# AntennaSide.net
KiCad netlist of a schematic drawn in Altium Designer
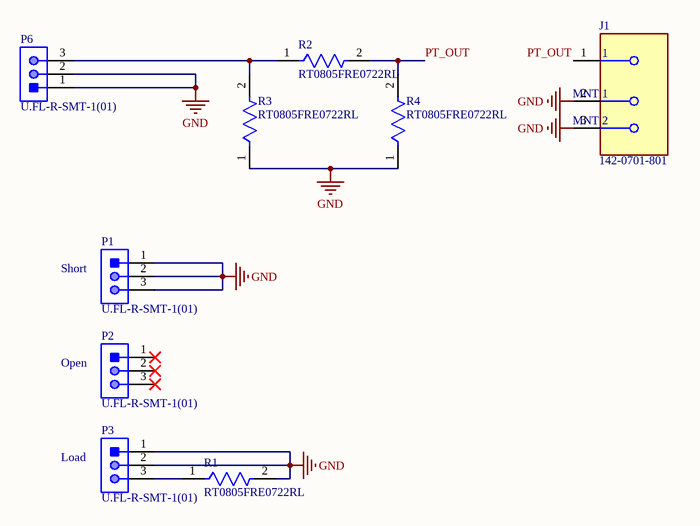
[diagram p0: AntennaSide.SchDoc]

(export (version "E")
  (design (tool "Eeschema 10.0.6"))
  (components
    (comp (ref "J1")
      (value "142-0701-801")
      (footprint "FP-142-0701-801-MFG")
      (description "CONN SMA JACK STR 50OHM EDGE MNT")
      (libsource (lib "Altium Content Vault") (part "89929399afe843c8b6880c6cbd0f99a"))
    )
    (comp (ref "P1")
      (value "U.FL-R-SMT-1(01)")
      (footprint "HRS-U.FL-R-SMT-3_V")
      (description "Ultra Small Coaxial Connector, 6 GHz, -40 to 90 degC, 3-Pin SMD, RoHS, Bulk")
      (fields (field (name "MANUFACTURER") "Hirose Electric"))
      (libsource (lib "Altium Content Vault") (part "CN-1P-M-R3"))
    )
    (comp (ref "P2")
      (value "U.FL-R-SMT-1(01)")
      (footprint "HRS-U.FL-R-SMT-3_V")
      (description "Ultra Small Coaxial Connector, 6 GHz, -40 to 90 degC, 3-Pin SMD, RoHS, Bulk")
      (fields (field (name "MANUFACTURER") "Hirose Electric"))
      (libsource (lib "Altium Content Vault") (part "CN-1P-M-R3"))
    )
    (comp (ref "P3")
      (value "U.FL-R-SMT-1(01)")
      (footprint "HRS-U.FL-R-SMT-3_V")
      (description "Ultra Small Coaxial Connector, 6 GHz, -40 to 90 degC, 3-Pin SMD, RoHS, Bulk")
      (fields (field (name "MANUFACTURER") "Hirose Electric"))
      (libsource (lib "Altium Content Vault") (part "CN-1P-M-R3"))
    )
    (comp (ref "P6")
      (value "U.FL-R-SMT-1(01)")
      (footprint "HRS-U.FL-R-SMT-3_V")
      (description "Ultra Small Coaxial Connector, 6 GHz, -40 to 90 degC, 3-Pin SMD, RoHS, Bulk")
      (fields (field (name "MANUFACTURER") "Hirose Electric"))
      (libsource (lib "") (part "CN-1P-M-R3_1"))
    )
    (comp (ref "R1")
      (value "RT0805FRE0722RL")
      (footprint "FP-RT0805-MFG")
      (description "RES SMD 22 OHM 1% 1/8W 0805")
      (fields
        (field (name "OCTOPART") "https://octopart.com/rt0805fre0722rl-yageo-39984181")
        (field (name "MANUFACTURER") "Yageo")
      )
      (libsource (lib "Altium Content Vault") (part "1029c3af85768c4190bb7ad29bc67b5"))
    )
    (comp (ref "R2")
      (value "RT0805FRE0722RL")
      (footprint "FP-RT0805-MFG")
      (description "RES SMD 22 OHM 1% 1/8W 0805")
      (fields
        (field (name "OCTOPART") "https://octopart.com/rt0805fre0722rl-yageo-39984181")
        (field (name "MANUFACTURER") "Yageo")
      )
      (libsource (lib "Altium Content Vault") (part "1029c3af85768c4190bb7ad29bc67b5"))
    )
    (comp (ref "R3")
      (value "RT0805FRE0722RL")
      (footprint "FP-RT0805-MFG")
      (description "RES SMD 22 OHM 1% 1/8W 0805")
      (fields
        (field (name "OCTOPART") "https://octopart.com/rt0805fre0722rl-yageo-39984181")
        (field (name "MANUFACTURER") "Yageo")
      )
      (libsource (lib "Altium Content Vault") (part "1029c3af85768c4190bb7ad29bc67b5"))
    )
    (comp (ref "R4")
      (value "RT0805FRE0722RL")
      (footprint "FP-RT0805-MFG")
      (description "RES SMD 22 OHM 1% 1/8W 0805")
      (fields
        (field (name "OCTOPART") "https://octopart.com/rt0805fre0722rl-yageo-39984181")
        (field (name "MANUFACTURER") "Yageo")
      )
      (libsource (lib "Altium Content Vault") (part "1029c3af85768c4190bb7ad29bc67b5"))
    )
  )
  (nets
    (net (code "1") (name "/PT_OUT") (class "Default")
      (node (ref "J1") (pin "1") (pinfunction "1_1") (pintype "passive"))
      (node (ref "R2") (pin "2") (pinfunction "2_2") (pintype "passive"))
      (node (ref "R4") (pin "2") (pinfunction "2_2") (pintype "passive"))
    )
    (net (code "2") (name "GND") (class "Default")
      (node (ref "J1") (pin "2") (pinfunction "MNT_1_2") (pintype "passive"))
      (node (ref "J1") (pin "3") (pinfunction "MNT_2_3") (pintype "passive"))
      (node (ref "P1") (pin "1") (pinfunction "1_1") (pintype "passive"))
      (node (ref "P1") (pin "2") (pinfunction "2_2") (pintype "passive"))
      (node (ref "P1") (pin "3") (pinfunction "3_3") (pintype "passive"))
      (node (ref "P3") (pin "1") (pinfunction "1_1") (pintype "passive"))
      (node (ref "P3") (pin "2") (pinfunction "2_2") (pintype "passive"))
      (node (ref "P6") (pin "1") (pinfunction "1_1") (pintype "passive"))
      (node (ref "P6") (pin "2") (pinfunction "2_2") (pintype "passive"))
      (node (ref "R1") (pin "2") (pinfunction "2_2") (pintype "passive"))
      (node (ref "R3") (pin "1") (pinfunction "1_1") (pintype "passive"))
      (node (ref "R4") (pin "1") (pinfunction "1_1") (pintype "passive"))
    )
    (net (code "3") (name "Net-(P3-Pad3)") (class "Default")
      (node (ref "P3") (pin "3") (pinfunction "3_3") (pintype "passive"))
      (node (ref "R1") (pin "1") (pinfunction "1_1") (pintype "passive"))
    )
    (net (code "4") (name "Net-(P6-Pad3)") (class "Default")
      (node (ref "P6") (pin "3") (pinfunction "3_3") (pintype "passive"))
      (node (ref "R2") (pin "1") (pinfunction "1_1") (pintype "passive"))
      (node (ref "R3") (pin "2") (pinfunction "2_2") (pintype "passive"))
    )
    (net (code "5") (name "unconnected-(P2-Pad1)") (class "Default")
      (node (ref "P2") (pin "1") (pinfunction "1_1") (pintype "passive+no_connect"))
    )
    (net (code "6") (name "unconnected-(P2-Pad2)") (class "Default")
      (node (ref "P2") (pin "2") (pinfunction "2_2") (pintype "passive+no_connect"))
    )
    (net (code "7") (name "unconnected-(P2-Pad3)") (class "Default")
      (node (ref "P2") (pin "3") (pinfunction "3_3") (pintype "passive+no_connect"))
    )
  )
)
